# Main.net
KiCad netlist of a schematic drawn in Altium Designer
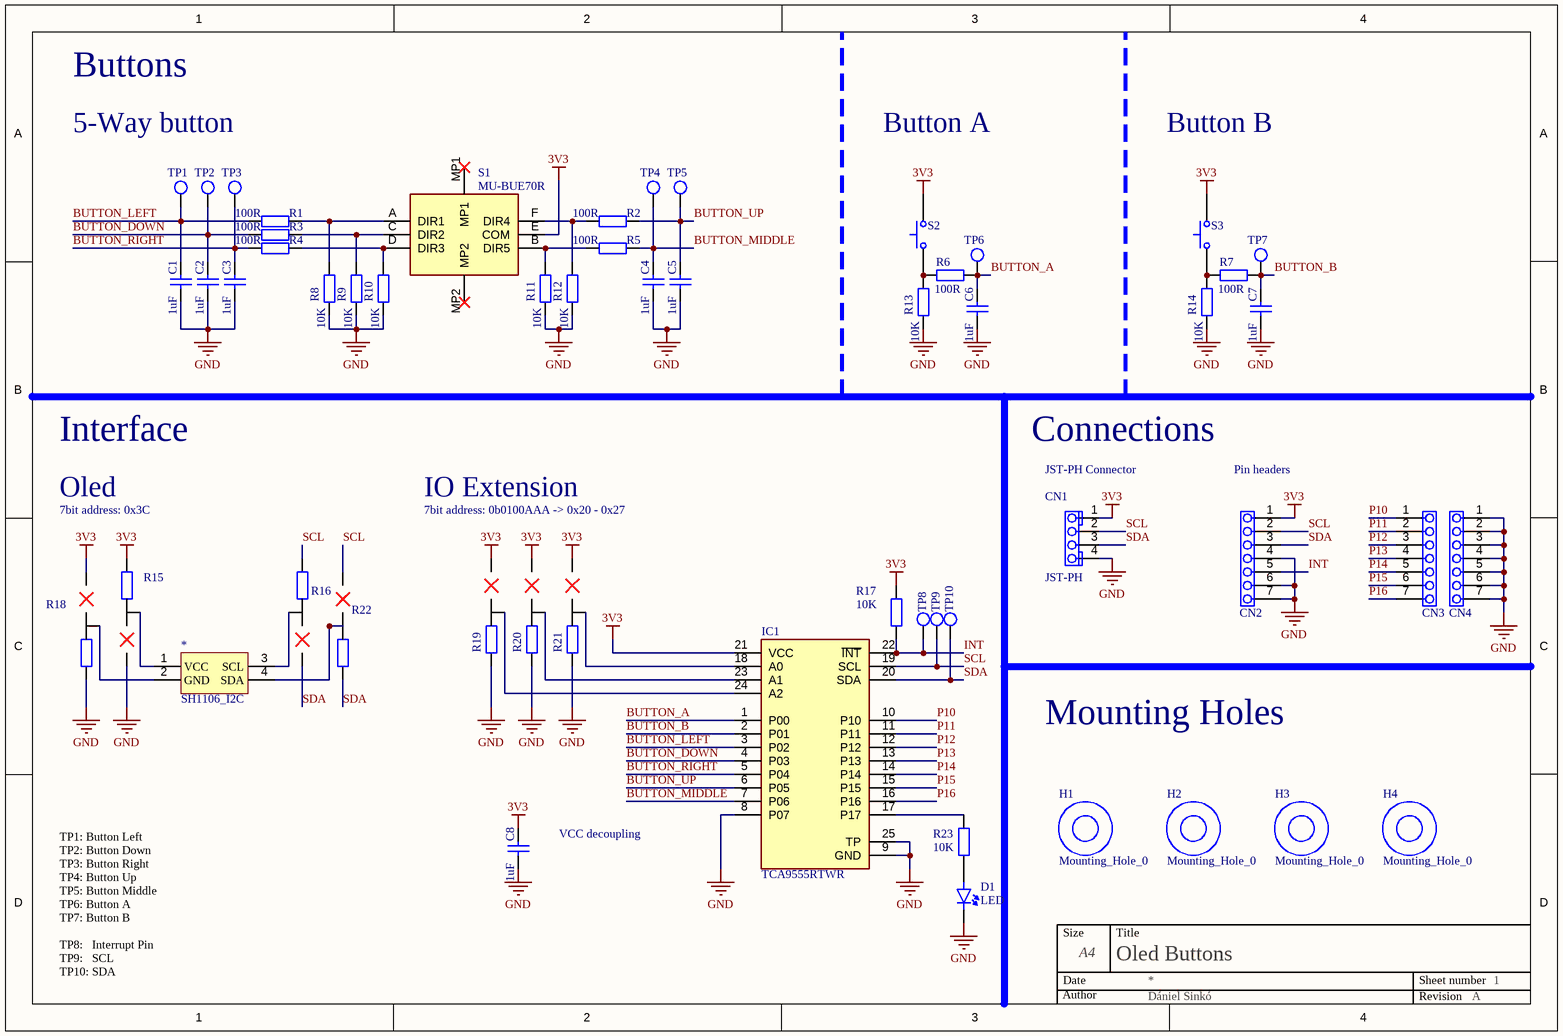
[diagram p0: Main.SchDoc]

(export (version "E")
  (design (tool "Eeschema 10.0.6"))
  (components
    (comp (ref "*")
      (value "SH1106_I2C")
      (footprint "SH1106_I2C")
      (libsource (lib "Generic_Schematic_Symbols") (part "SH1106_I2C"))
    )
    (comp (ref "C1")
      (value "1uF")
      (footprint "CAP0603")
      (description "Capacitor")
      (fields (field (name "VOLTAGE") "25V") (field (name "LCSC PART NUMBER") "C29936"))
      (libsource (lib "Components") (part "1uF"))
    )
    (comp (ref "C2")
      (value "1uF")
      (footprint "CAP0603")
      (description "Capacitor")
      (fields (field (name "VOLTAGE") "25V") (field (name "LCSC PART NUMBER") "C29936"))
      (libsource (lib "Components") (part "1uF"))
    )
    (comp (ref "C3")
      (value "1uF")
      (footprint "CAP0603")
      (description "Capacitor")
      (fields (field (name "VOLTAGE") "25V") (field (name "LCSC PART NUMBER") "C29936"))
      (libsource (lib "Components") (part "1uF"))
    )
    (comp (ref "C4")
      (value "1uF")
      (footprint "CAP0603")
      (description "Capacitor")
      (fields (field (name "VOLTAGE") "25V") (field (name "LCSC PART NUMBER") "C29936"))
      (libsource (lib "Components") (part "1uF"))
    )
    (comp (ref "C5")
      (value "1uF")
      (footprint "CAP0603")
      (description "Capacitor")
      (fields (field (name "VOLTAGE") "25V") (field (name "LCSC PART NUMBER") "C29936"))
      (libsource (lib "Components") (part "1uF"))
    )
    (comp (ref "C6")
      (value "1uF")
      (footprint "CAP0603")
      (description "Capacitor")
      (fields (field (name "VOLTAGE") "25V") (field (name "LCSC PART NUMBER") "C29936"))
      (libsource (lib "Components") (part "1uF"))
    )
    (comp (ref "C7")
      (value "1uF")
      (footprint "CAP0603")
      (description "Capacitor")
      (fields (field (name "VOLTAGE") "25V") (field (name "LCSC PART NUMBER") "C29936"))
      (libsource (lib "Components") (part "1uF"))
    )
    (comp (ref "C8")
      (value "1uF")
      (footprint "CAP0603")
      (description "Capacitor")
      (fields (field (name "VOLTAGE") "25V") (field (name "LCSC PART NUMBER") "C29936"))
      (libsource (lib "Components") (part "1uF"))
    )
    (comp (ref "CN1")
      (value "JST-PH")
      (footprint "JST-PH-1x4-THT-RIGHT")
      (description "JST-PH-1x4 2mm")
      (fields
        (field (name "MOUSER PART NUMBER") "306-B03BPASKLFSN")
        (field (name "LCSC PART NUMBER") "C131334")
      )
      (libsource (lib "Generic_Schematic_Symbols") (part "JST-PH-1x4"))
    )
    (comp (ref "CN2")
      (value "Pins 1x7")
      (footprint "PIN-1X7")
      (description "2.54mm")
      (libsource (lib "Generic_Schematic_Symbols") (part "Pin-1x7"))
    )
    (comp (ref "CN3")
      (value "Pins 1x7")
      (footprint "PIN-1X7")
      (description "2.54mm")
      (libsource (lib "Generic_Schematic_Symbols") (part "Pin-1x7"))
    )
    (comp (ref "CN4")
      (value "Pins 1x7")
      (footprint "PIN-1X7")
      (description "2.54mm")
      (libsource (lib "Generic_Schematic_Symbols") (part "Pin-1x7"))
    )
    (comp (ref "D1")
      (value "LED")
      (footprint "LED0603")
      (description "Light Emitting Diode")
      (fields (field (name "LCSC PART NUMBER") "C965800"))
      (libsource (lib "Components") (part "LED"))
    )
    (comp (ref "H1")
      (value "Mounting_Hole_0")
      (footprint "MOUNTING_HOLE_M3_0")
      (description "Mounting hole with no connectivity.")
      (libsource (lib "Generic_Schematic_Symbols") (part "Mounting_Hole_0"))
    )
    (comp (ref "H2")
      (value "Mounting_Hole_0")
      (footprint "MOUNTING_HOLE_M3_0")
      (description "Mounting hole with no connectivity.")
      (libsource (lib "Generic_Schematic_Symbols") (part "Mounting_Hole_0"))
    )
    (comp (ref "H3")
      (value "Mounting_Hole_0")
      (footprint "MOUNTING_HOLE_M3_0")
      (description "Mounting hole with no connectivity.")
      (libsource (lib "Generic_Schematic_Symbols") (part "Mounting_Hole_0"))
    )
    (comp (ref "H4")
      (value "Mounting_Hole_0")
      (footprint "MOUNTING_HOLE_M3_0")
      (description "Mounting hole with no connectivity.")
      (libsource (lib "Generic_Schematic_Symbols") (part "Mounting_Hole_0"))
    )
    (comp (ref "IC1")
      (value "TCA9555RTWR")
      (footprint "WQFN-24")
      (description "Integrated Circuit")
      (fields
        (field (name "MOUSER PART NUMBER") "595-TCA9555RTWR")
        (field (name "LCSC PART NUMBER") "C42420609")
      )
      (libsource (lib "Generic_Schematic_Symbols") (part "TCA9555RTWR"))
    )
    (comp (ref "R1")
      (value "100R")
      (footprint "RES0603")
      (description "Resistor")
      (fields (field (name "LCSC PART NUMBER") "C105588"))
      (libsource (lib "Components") (part "100R"))
    )
    (comp (ref "R2")
      (value "100R")
      (footprint "RES0603")
      (description "Resistor")
      (fields (field (name "LCSC PART NUMBER") "C105588"))
      (libsource (lib "Components") (part "100R"))
    )
    (comp (ref "R3")
      (value "100R")
      (footprint "RES0603")
      (description "Resistor")
      (fields (field (name "LCSC PART NUMBER") "C105588"))
      (libsource (lib "Components") (part "100R"))
    )
    (comp (ref "R4")
      (value "100R")
      (footprint "RES0603")
      (description "Resistor")
      (fields (field (name "LCSC PART NUMBER") "C105588"))
      (libsource (lib "Components") (part "100R"))
    )
    (comp (ref "R5")
      (value "100R")
      (footprint "RES0603")
      (description "Resistor")
      (fields (field (name "LCSC PART NUMBER") "C105588"))
      (libsource (lib "Components") (part "100R"))
    )
    (comp (ref "R6")
      (value "100R")
      (footprint "RES0603")
      (description "Resistor")
      (fields (field (name "LCSC PART NUMBER") "C105588"))
      (libsource (lib "Components") (part "100R"))
    )
    (comp (ref "R7")
      (value "100R")
      (footprint "RES0603")
      (description "Resistor")
      (fields (field (name "LCSC PART NUMBER") "C105588"))
      (libsource (lib "Components") (part "100R"))
    )
    (comp (ref "R8")
      (value "10K")
      (footprint "RES0603")
      (description "Resistor")
      (fields (field (name "LCSC PART NUMBER") "C98220"))
      (libsource (lib "Components") (part "10K"))
    )
    (comp (ref "R9")
      (value "10K")
      (footprint "RES0603")
      (description "Resistor")
      (fields (field (name "LCSC PART NUMBER") "C98220"))
      (libsource (lib "Components") (part "10K"))
    )
    (comp (ref "R10")
      (value "10K")
      (footprint "RES0603")
      (description "Resistor")
      (fields (field (name "LCSC PART NUMBER") "C98220"))
      (libsource (lib "Components") (part "10K"))
    )
    (comp (ref "R11")
      (value "10K")
      (footprint "RES0603")
      (description "Resistor")
      (fields (field (name "LCSC PART NUMBER") "C98220"))
      (libsource (lib "Components") (part "10K"))
    )
    (comp (ref "R12")
      (value "10K")
      (footprint "RES0603")
      (description "Resistor")
      (fields (field (name "LCSC PART NUMBER") "C98220"))
      (libsource (lib "Components") (part "10K"))
    )
    (comp (ref "R13")
      (value "10K")
      (footprint "RES0603")
      (description "Resistor")
      (fields (field (name "LCSC PART NUMBER") "C98220"))
      (libsource (lib "Components") (part "10K"))
    )
    (comp (ref "R14")
      (value "10K")
      (footprint "RES0603")
      (description "Resistor")
      (fields (field (name "LCSC PART NUMBER") "C98220"))
      (libsource (lib "Components") (part "10K"))
    )
    (comp (ref "R15")
      (value "0R")
      (footprint "RES0603_SELECTION")
      (description "Resistor selection between 2 value.")
      (fields (field (name "LCSC PART NUMBER") "C2906974"))
      (libsource (lib "Generic_Schematic_Symbols") (part "Resistor_Selection"))
    )
    (comp (ref "R16")
      (value "0R")
      (footprint "RES0603_SELECTION")
      (description "Resistor selection between 2 value.")
      (fields (field (name "LCSC PART NUMBER") "C2906974"))
      (libsource (lib "") (part "Resistor_Selection_3"))
    )
    (comp (ref "R17")
      (value "10K")
      (footprint "RES0603")
      (description "Resistor")
      (fields (field (name "LCSC PART NUMBER") "C98220"))
      (libsource (lib "Components") (part "10K"))
    )
    (comp (ref "R18")
      (value "0R")
      (footprint "RES0603_SELECTION")
      (description "Resistor selection between 2 value.")
      (fields (field (name "LCSC PART NUMBER") "C2906974"))
      (libsource (lib "") (part "Resistor_Selection_1"))
    )
    (comp (ref "R19")
      (value "0R")
      (footprint "RES0603_SELECTION")
      (description "Resistor selection between 2 value.")
      (fields (field (name "LCSC PART NUMBER") "C2906974"))
      (libsource (lib "") (part "Resistor_Selection_1"))
    )
    (comp (ref "R20")
      (value "0R")
      (footprint "RES0603_SELECTION")
      (description "Resistor selection between 2 value.")
      (fields (field (name "LCSC PART NUMBER") "C2906974"))
      (libsource (lib "") (part "Resistor_Selection_1"))
    )
    (comp (ref "R21")
      (value "0R")
      (footprint "RES0603_SELECTION")
      (description "Resistor selection between 2 value.")
      (fields (field (name "LCSC PART NUMBER") "C2906974"))
      (libsource (lib "") (part "Resistor_Selection_1"))
    )
    (comp (ref "R22")
      (value "0R")
      (footprint "RES0603_SELECTION")
      (description "Resistor selection between 2 value.")
      (fields (field (name "LCSC PART NUMBER") "C2906974"))
      (libsource (lib "") (part "Resistor_Selection_2"))
    )
    (comp (ref "R23")
      (value "10K")
      (footprint "RES0603")
      (description "Resistor")
      (fields (field (name "LCSC PART NUMBER") "C98220"))
      (libsource (lib "Components") (part "10K"))
    )
    (comp (ref "S1")
      (value "MU-BUE70R")
      (footprint "MUBUE70R")
      (description "Switch")
      (fields (field (name "LCSC PART NUMBER") "C2858287"))
      (libsource (lib "Buttons") (part "MU-BUE70R"))
    )
    (comp (ref "S2")
      (value "Tactile switch")
      (footprint "TS046673BK100SMT")
      (description "Switch (2-Pin Push)\r\nMouser and LCSC connection are different! Use only opposite corner pins.")
      (fields
        (field (name "MOUSER PART NUMBER") "179-TS046673BK100SMT")
        (field (name "LCSC PART NUMBER") "C49234152")
      )
      (libsource (lib "Buttons") (part "Tactile switch"))
    )
    (comp (ref "S3")
      (value "Tactile switch")
      (footprint "TS046673BK100SMT")
      (description "Switch (2-Pin Push)\r\nMouser and LCSC connection are different! Use only opposite corner pins.")
      (fields
        (field (name "MOUSER PART NUMBER") "179-TS046673BK100SMT")
        (field (name "LCSC PART NUMBER") "C49234152")
      )
      (libsource (lib "Buttons") (part "Tactile switch"))
    )
    (comp (ref "TP1")
      (value "Test Point")
      (footprint "TP_PAD")
      (libsource (lib "Generic_Schematic_Symbols") (part "Test Point"))
    )
    (comp (ref "TP2")
      (value "Test Point")
      (footprint "TP_PAD")
      (libsource (lib "Generic_Schematic_Symbols") (part "Test Point"))
    )
    (comp (ref "TP3")
      (value "Test Point")
      (footprint "TP_PAD")
      (libsource (lib "Generic_Schematic_Symbols") (part "Test Point"))
    )
    (comp (ref "TP4")
      (value "Test Point")
      (footprint "TP_PAD")
      (libsource (lib "Generic_Schematic_Symbols") (part "Test Point"))
    )
    (comp (ref "TP5")
      (value "Test Point")
      (footprint "TP_PAD")
      (libsource (lib "Generic_Schematic_Symbols") (part "Test Point"))
    )
    (comp (ref "TP6")
      (value "Test Point")
      (footprint "TP_PAD")
      (libsource (lib "Generic_Schematic_Symbols") (part "Test Point"))
    )
    (comp (ref "TP7")
      (value "Test Point")
      (footprint "TP_PAD")
      (libsource (lib "Generic_Schematic_Symbols") (part "Test Point"))
    )
    (comp (ref "TP8")
      (value "Test Point")
      (footprint "TP_PAD")
      (libsource (lib "Generic_Schematic_Symbols") (part "Test Point"))
    )
    (comp (ref "TP9")
      (value "Test Point")
      (footprint "TP_PAD")
      (libsource (lib "Generic_Schematic_Symbols") (part "Test Point"))
    )
    (comp (ref "TP10")
      (value "Test Point")
      (footprint "TP_PAD")
      (libsource (lib "Generic_Schematic_Symbols") (part "Test Point"))
    )
  )
  (nets
    (net (code "1") (name "/BUTTON_A") (class "Default")
      (node (ref "C6") (pin "2") (pinfunction "2_2") (pintype "passive"))
      (node (ref "IC1") (pin "1") (pinfunction "P00_1") (pintype "passive"))
      (node (ref "R6") (pin "2") (pinfunction "2_2") (pintype "passive"))
      (node (ref "TP6") (pin "1") (pintype "passive"))
    )
    (net (code "2") (name "/BUTTON_B") (class "Default")
      (node (ref "C7") (pin "2") (pinfunction "2_2") (pintype "passive"))
      (node (ref "IC1") (pin "2") (pinfunction "P01_2") (pintype "passive"))
      (node (ref "R7") (pin "2") (pinfunction "2_2") (pintype "passive"))
      (node (ref "TP7") (pin "1") (pintype "passive"))
    )
    (net (code "3") (name "/BUTTON_DOWN") (class "Default")
      (node (ref "C2") (pin "2") (pinfunction "2_2") (pintype "passive"))
      (node (ref "IC1") (pin "4") (pinfunction "P03_4") (pintype "passive"))
      (node (ref "R3") (pin "1") (pinfunction "1_1") (pintype "passive"))
      (node (ref "TP2") (pin "1") (pintype "passive"))
    )
    (net (code "4") (name "/BUTTON_LEFT") (class "Default")
      (node (ref "C1") (pin "2") (pinfunction "2_2") (pintype "passive"))
      (node (ref "IC1") (pin "3") (pinfunction "P02_3") (pintype "passive"))
      (node (ref "R1") (pin "1") (pinfunction "1_1") (pintype "passive"))
      (node (ref "TP1") (pin "1") (pintype "passive"))
    )
    (net (code "5") (name "/BUTTON_MIDDLE") (class "Default")
      (node (ref "C4") (pin "2") (pinfunction "2_2") (pintype "passive"))
      (node (ref "IC1") (pin "7") (pinfunction "P06_7") (pintype "passive"))
      (node (ref "R5") (pin "2") (pinfunction "2_2") (pintype "passive"))
      (node (ref "TP4") (pin "1") (pintype "passive"))
    )
    (net (code "6") (name "/BUTTON_RIGHT") (class "Default")
      (node (ref "C3") (pin "2") (pinfunction "2_2") (pintype "passive"))
      (node (ref "IC1") (pin "5") (pinfunction "P04_5") (pintype "passive"))
      (node (ref "R4") (pin "1") (pinfunction "1_1") (pintype "passive"))
      (node (ref "TP3") (pin "1") (pintype "passive"))
    )
    (net (code "7") (name "/BUTTON_UP") (class "Default")
      (node (ref "C5") (pin "2") (pinfunction "2_2") (pintype "passive"))
      (node (ref "IC1") (pin "6") (pinfunction "P05_6") (pintype "passive"))
      (node (ref "R2") (pin "2") (pinfunction "2_2") (pintype "passive"))
      (node (ref "TP5") (pin "1") (pintype "passive"))
    )
    (net (code "8") (name "/INT") (class "Default")
      (node (ref "CN2") (pin "5") (pinfunction "5_5") (pintype "passive"))
      (node (ref "IC1") (pin "22") (pinfunction "~{INT}_22") (pintype "passive"))
      (node (ref "R17") (pin "1") (pinfunction "1_1") (pintype "passive"))
      (node (ref "TP8") (pin "1") (pintype "passive"))
    )
    (net (code "9") (name "/P10") (class "Default")
      (node (ref "CN3") (pin "1") (pinfunction "1_1") (pintype "passive"))
      (node (ref "IC1") (pin "10") (pinfunction "P10_10") (pintype "passive"))
    )
    (net (code "10") (name "/P11") (class "Default")
      (node (ref "CN3") (pin "2") (pinfunction "2_2") (pintype "passive"))
      (node (ref "IC1") (pin "11") (pinfunction "P11_11") (pintype "passive"))
    )
    (net (code "11") (name "/P12") (class "Default")
      (node (ref "CN3") (pin "3") (pinfunction "3_3") (pintype "passive"))
      (node (ref "IC1") (pin "12") (pinfunction "P12_12") (pintype "passive"))
    )
    (net (code "12") (name "/P13") (class "Default")
      (node (ref "CN3") (pin "4") (pinfunction "4_4") (pintype "passive"))
      (node (ref "IC1") (pin "13") (pinfunction "P13_13") (pintype "passive"))
    )
    (net (code "13") (name "/P14") (class "Default")
      (node (ref "CN3") (pin "5") (pinfunction "5_5") (pintype "passive"))
      (node (ref "IC1") (pin "14") (pinfunction "P14_14") (pintype "passive"))
    )
    (net (code "14") (name "/P15") (class "Default")
      (node (ref "CN3") (pin "6") (pinfunction "6_6") (pintype "passive"))
      (node (ref "IC1") (pin "15") (pinfunction "P15_15") (pintype "passive"))
    )
    (net (code "15") (name "/P16") (class "Default")
      (node (ref "CN3") (pin "7") (pinfunction "7_7") (pintype "passive"))
      (node (ref "IC1") (pin "16") (pinfunction "P16_16") (pintype "passive"))
    )
    (net (code "16") (name "/SCL") (class "Default")
      (node (ref "CN1") (pin "2") (pinfunction "2_2") (pintype "passive"))
      (node (ref "CN2") (pin "2") (pinfunction "2_2") (pintype "passive"))
      (node (ref "IC1") (pin "19") (pinfunction "SCL_19") (pintype "passive"))
      (node (ref "R16") (pin "1") (pinfunction "1_1") (pintype "passive"))
      (node (ref "R22") (pin "3") (pinfunction "3_3") (pintype "passive"))
      (node (ref "TP9") (pin "1") (pintype "passive"))
    )
    (net (code "17") (name "/SDA") (class "Default")
      (node (ref "CN1") (pin "3") (pinfunction "3_3") (pintype "passive"))
      (node (ref "CN2") (pin "3") (pinfunction "3_3") (pintype "passive"))
      (node (ref "IC1") (pin "20") (pinfunction "SDA_20") (pintype "passive"))
      (node (ref "R16") (pin "3") (pinfunction "3_3") (pintype "passive"))
      (node (ref "R22") (pin "1") (pinfunction "1_1") (pintype "passive"))
      (node (ref "TP10") (pin "1") (pintype "passive"))
    )
    (net (code "18") (name "3V3") (class "Default")
      (node (ref "C8") (pin "2") (pinfunction "2_2") (pintype "passive"))
      (node (ref "CN1") (pin "1") (pinfunction "1_1") (pintype "passive"))
      (node (ref "CN2") (pin "1") (pinfunction "1_1") (pintype "passive"))
      (node (ref "IC1") (pin "21") (pinfunction "VCC_21") (pintype "passive"))
      (node (ref "R15") (pin "1") (pinfunction "1_1") (pintype "passive"))
      (node (ref "R17") (pin "2") (pinfunction "2_2") (pintype "passive"))
      (node (ref "R18") (pin "3") (pinfunction "3_3") (pintype "passive"))
      (node (ref "R19") (pin "3") (pinfunction "3_3") (pintype "passive"))
      (node (ref "R20") (pin "3") (pinfunction "3_3") (pintype "passive"))
      (node (ref "R21") (pin "3") (pinfunction "3_3") (pintype "passive"))
      (node (ref "S1") (pin "E") (pinfunction "COM_E") (pintype "passive"))
      (node (ref "S2") (pin "4") (pinfunction "4_4") (pintype "passive"))
      (node (ref "S3") (pin "4") (pinfunction "4_4") (pintype "passive"))
    )
    (net (code "19") (name "GND") (class "Default")
      (node (ref "C1") (pin "1") (pinfunction "1_1") (pintype "passive"))
      (node (ref "C2") (pin "1") (pinfunction "1_1") (pintype "passive"))
      (node (ref "C3") (pin "1") (pinfunction "1_1") (pintype "passive"))
      (node (ref "C4") (pin "1") (pinfunction "1_1") (pintype "passive"))
      (node (ref "C5") (pin "1") (pinfunction "1_1") (pintype "passive"))
      (node (ref "C6") (pin "1") (pinfunction "1_1") (pintype "passive"))
      (node (ref "C7") (pin "1") (pinfunction "1_1") (pintype "passive"))
      (node (ref "C8") (pin "1") (pinfunction "1_1") (pintype "passive"))
      (node (ref "CN1") (pin "4") (pinfunction "4_4") (pintype "passive"))
      (node (ref "CN2") (pin "4") (pinfunction "4_4") (pintype "passive"))
      (node (ref "CN2") (pin "6") (pinfunction "6_6") (pintype "passive"))
      (node (ref "CN2") (pin "7") (pinfunction "7_7") (pintype "passive"))
      (node (ref "CN4") (pin "1") (pinfunction "1_1") (pintype "passive"))
      (node (ref "CN4") (pin "2") (pinfunction "2_2") (pintype "passive"))
      (node (ref "CN4") (pin "3") (pinfunction "3_3") (pintype "passive"))
      (node (ref "CN4") (pin "4") (pinfunction "4_4") (pintype "passive"))
      (node (ref "CN4") (pin "5") (pinfunction "5_5") (pintype "passive"))
      (node (ref "CN4") (pin "6") (pinfunction "6_6") (pintype "passive"))
      (node (ref "CN4") (pin "7") (pinfunction "7_7") (pintype "passive"))
      (node (ref "D1") (pin "C") (pinfunction "C_C") (pintype "passive"))
      (node (ref "IC1") (pin "25") (pinfunction "TP_25") (pintype "passive"))
      (node (ref "IC1") (pin "8") (pinfunction "P07_8") (pintype "passive"))
      (node (ref "IC1") (pin "9") (pinfunction "GND_9") (pintype "passive"))
      (node (ref "R10") (pin "1") (pinfunction "1_1") (pintype "passive"))
      (node (ref "R11") (pin "1") (pinfunction "1_1") (pintype "passive"))
      (node (ref "R12") (pin "1") (pinfunction "1_1") (pintype "passive"))
      (node (ref "R13") (pin "1") (pinfunction "1_1") (pintype "passive"))
      (node (ref "R14") (pin "1") (pinfunction "1_1") (pintype "passive"))
      (node (ref "R15") (pin "3") (pinfunction "3_3") (pintype "passive"))
      (node (ref "R18") (pin "1") (pinfunction "1_1") (pintype "passive"))
      (node (ref "R19") (pin "1") (pinfunction "1_1") (pintype "passive"))
      (node (ref "R20") (pin "1") (pinfunction "1_1") (pintype "passive"))
      (node (ref "R21") (pin "1") (pinfunction "1_1") (pintype "passive"))
      (node (ref "R8") (pin "1") (pinfunction "1_1") (pintype "passive"))
      (node (ref "R9") (pin "1") (pinfunction "1_1") (pintype "passive"))
    )
    (net (code "20") (name "Net-(*-GND)") (class "Default")
      (node (ref "*") (pin "2") (pinfunction "GND_2") (pintype "passive"))
      (node (ref "R18") (pin "2") (pinfunction "2_2") (pintype "passive"))
    )
    (net (code "21") (name "Net-(*-SCL)") (class "Default")
      (node (ref "*") (pin "3") (pinfunction "SCL_3") (pintype "passive"))
      (node (ref "R16") (pin "2") (pinfunction "2_2") (pintype "passive"))
    )
    (net (code "22") (name "Net-(*-SDA)") (class "Default")
      (node (ref "*") (pin "4") (pinfunction "SDA_4") (pintype "passive"))
      (node (ref "R22") (pin "2") (pinfunction "2_2") (pintype "passive"))
    )
    (net (code "23") (name "Net-(*-VCC)") (class "Default")
      (node (ref "*") (pin "1") (pinfunction "VCC_1") (pintype "passive"))
      (node (ref "R15") (pin "2") (pinfunction "2_2") (pintype "passive"))
    )
    (net (code "24") (name "Net-(D1-PadA)") (class "Default")
      (node (ref "D1") (pin "A") (pinfunction "A_A") (pintype "passive"))
      (node (ref "R23") (pin "1") (pinfunction "1_1") (pintype "passive"))
    )
    (net (code "25") (name "Net-(IC1-A0)") (class "Default")
      (node (ref "IC1") (pin "18") (pinfunction "A0_18") (pintype "passive"))
      (node (ref "R21") (pin "2") (pinfunction "2_2") (pintype "passive"))
    )
    (net (code "26") (name "Net-(IC1-A1)") (class "Default")
      (node (ref "IC1") (pin "23") (pinfunction "A1_23") (pintype "passive"))
      (node (ref "R20") (pin "2") (pinfunction "2_2") (pintype "passive"))
    )
    (net (code "27") (name "Net-(IC1-A2)") (class "Default")
      (node (ref "IC1") (pin "24") (pinfunction "A2_24") (pintype "passive"))
      (node (ref "R19") (pin "2") (pinfunction "2_2") (pintype "passive"))
    )
    (net (code "28") (name "Net-(IC1-P17)") (class "Default")
      (node (ref "IC1") (pin "17") (pinfunction "P17_17") (pintype "passive"))
      (node (ref "R23") (pin "2") (pinfunction "2_2") (pintype "passive"))
    )
    (net (code "29") (name "Net-(R13-Pad2)") (class "Default")
      (node (ref "R13") (pin "2") (pinfunction "2_2") (pintype "passive"))
      (node (ref "R6") (pin "1") (pinfunction "1_1") (pintype "passive"))
      (node (ref "S2") (pin "1") (pinfunction "1_1") (pintype "passive"))
    )
    (net (code "30") (name "Net-(R14-Pad2)") (class "Default")
      (node (ref "R14") (pin "2") (pinfunction "2_2") (pintype "passive"))
      (node (ref "R7") (pin "1") (pinfunction "1_1") (pintype "passive"))
      (node (ref "S3") (pin "1") (pinfunction "1_1") (pintype "passive"))
    )
    (net (code "31") (name "Net-(S1-DIR1)") (class "Default")
      (node (ref "R1") (pin "2") (pinfunction "2_2") (pintype "passive"))
      (node (ref "R8") (pin "2") (pinfunction "2_2") (pintype "passive"))
      (node (ref "S1") (pin "A") (pinfunction "DIR1_A") (pintype "passive"))
    )
    (net (code "32") (name "Net-(S1-DIR2)") (class "Default")
      (node (ref "R3") (pin "2") (pinfunction "2_2") (pintype "passive"))
      (node (ref "R9") (pin "2") (pinfunction "2_2") (pintype "passive"))
      (node (ref "S1") (pin "C") (pinfunction "DIR2_C") (pintype "passive"))
    )
    (net (code "33") (name "Net-(S1-DIR3)") (class "Default")
      (node (ref "R10") (pin "2") (pinfunction "2_2") (pintype "passive"))
      (node (ref "R4") (pin "2") (pinfunction "2_2") (pintype "passive"))
      (node (ref "S1") (pin "D") (pinfunction "DIR3_D") (pintype "passive"))
    )
    (net (code "34") (name "Net-(S1-DIR4)") (class "Default")
      (node (ref "R12") (pin "2") (pinfunction "2_2") (pintype "passive"))
      (node (ref "R2") (pin "1") (pinfunction "1_1") (pintype "passive"))
      (node (ref "S1") (pin "F") (pinfunction "DIR4_F") (pintype "passive"))
    )
    (net (code "35") (name "Net-(S1-DIR5)") (class "Default")
      (node (ref "R11") (pin "2") (pinfunction "2_2") (pintype "passive"))
      (node (ref "R5") (pin "1") (pinfunction "1_1") (pintype "passive"))
      (node (ref "S1") (pin "B") (pinfunction "DIR5_B") (pintype "passive"))
    )
    (net (code "36") (name "unconnected-(S1-PadMP1)") (class "Default")
      (node (ref "S1") (pin "MP1") (pinfunction "MP1_MP1") (pintype "passive+no_connect"))
    )
    (net (code "37") (name "unconnected-(S1-PadMP2)") (class "Default")
      (node (ref "S1") (pin "MP2") (pinfunction "MP2_MP2") (pintype "passive+no_connect"))
    )
  )
)
